# plug-v19-Make-board-myself-to-test-circu.net
KiCad netlist of a schematic drawn in EAGLE
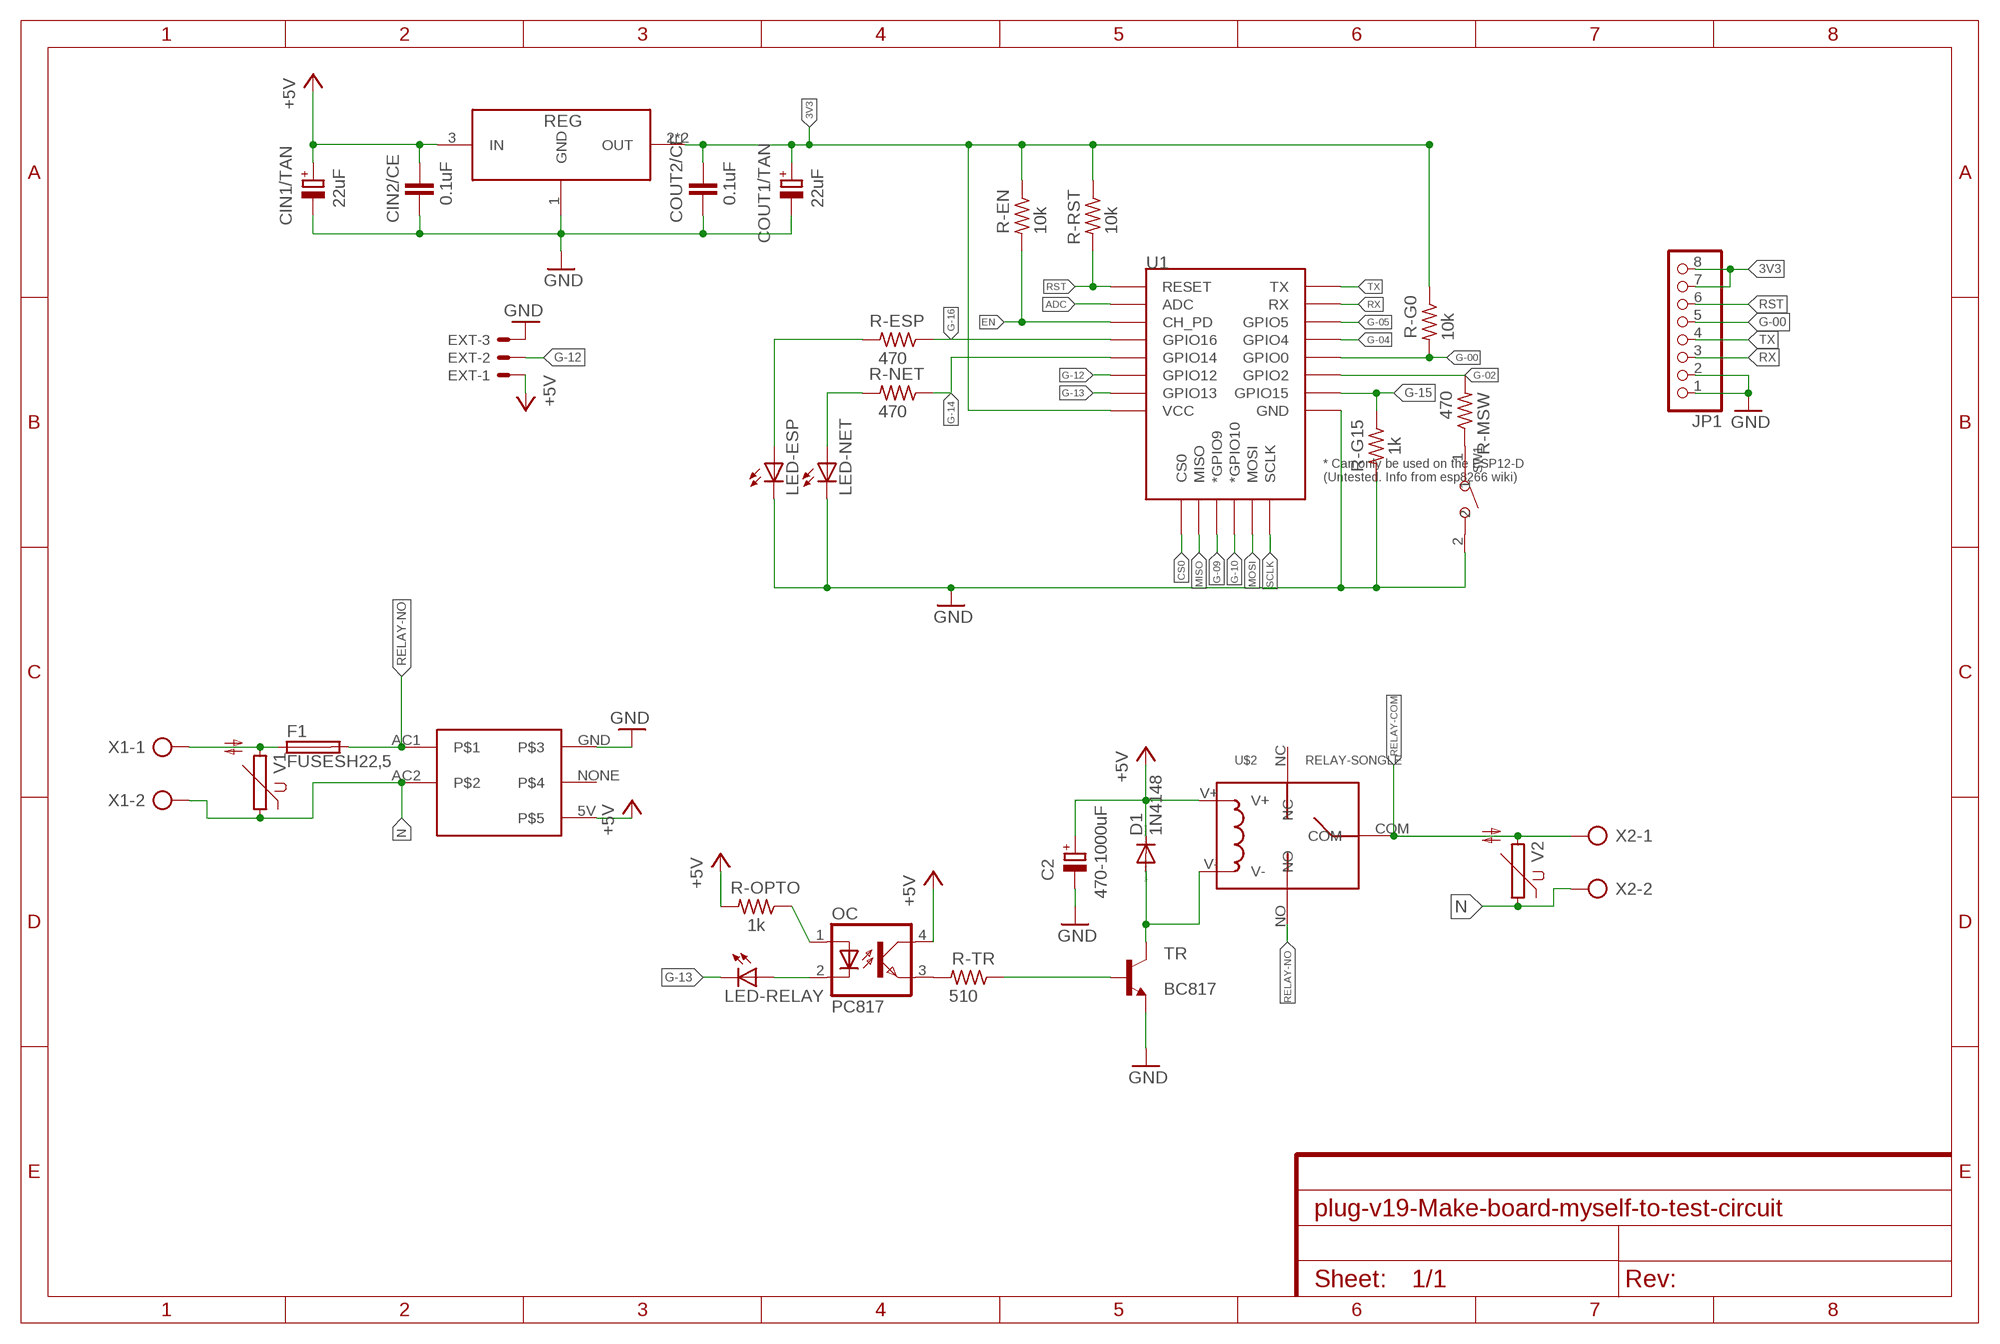
[diagram p0: schematic, sheet 1]

(export (version "E")
  (design (tool "Eeschema 10.0.6"))
  (components
    (comp (ref "C2")
      (value "470-1000uF")
      (footprint "eagle-import:E3,5-8")
      (libsource (lib "eagle-import") (part "CPOL-EUE3.5-8"))
    )
    (comp (ref "CIN1/TAN")
      (value "22uF")
      (footprint "eagle-import:B_3528-21R")
      (libsource (lib "eagle-import") (part "CPOL-EUB/3528-21R"))
    )
    (comp (ref "CIN2/CE")
      (value "0.1uF")
      (footprint "eagle-import:C0805K")
      (libsource (lib "eagle-import") (part "C-EUC0805K"))
    )
    (comp (ref "COUT1/TAN")
      (value "22uF")
      (footprint "eagle-import:B_3528-21R")
      (libsource (lib "eagle-import") (part "CPOL-EUB/3528-21R"))
    )
    (comp (ref "COUT2/CE")
      (value "0.1uF")
      (footprint "eagle-import:C0805K")
      (libsource (lib "eagle-import") (part "C-EUC0805K"))
    )
    (comp (ref "D1")
      (value "1N4148")
      (footprint "eagle-import:DO35-7")
      (libsource (lib "eagle-import") (part "1N4148DO35-7"))
    )
    (comp (ref "EXT")
      (value "53048-03")
      (footprint "eagle-import:53048-03")
      (fields (field (name "MF") "WALDOM/MOLEX") (field (name "MPN") "53048-0310"))
      (libsource (lib "eagle-import") (part "53?-03048"))
    )
    (comp (ref "F1")
      (value "FUSESH22,5")
      (footprint "eagle-import:SH22,5")
      (libsource (lib "eagle-import") (part "FUSESH22,5"))
    )
    (comp (ref "JP1")
      (value "PINHD-1X8")
      (footprint "eagle-import:1X08")
      (libsource (lib "eagle-import") (part "PINHD-1X8"))
    )
    (comp (ref "LED-ESP")
      (value "LEDCHIPLED_0805")
      (footprint "eagle-import:CHIPLED_0805")
      (libsource (lib "eagle-import") (part "LEDCHIPLED_0805"))
    )
    (comp (ref "LED-NET")
      (value "LEDCHIPLED_0805")
      (footprint "eagle-import:CHIPLED_0805")
      (libsource (lib "eagle-import") (part "LEDCHIPLED_0805"))
    )
    (comp (ref "LED-RELAY")
      (value "LEDCHIPLED_0805")
      (footprint "eagle-import:CHIPLED_0805")
      (libsource (lib "eagle-import") (part "LEDCHIPLED_0805"))
    )
    (comp (ref "OC")
      (value "PC817")
      (footprint "eagle-import:DIL04")
      (fields (field (name "MPN") "PC817X4J000F"))
      (libsource (lib "eagle-import") (part "PC817"))
    )
    (comp (ref "R-EN")
      (value "10k")
      (footprint "eagle-import:M0805")
      (libsource (lib "eagle-import") (part "R-US_M0805"))
    )
    (comp (ref "R-ESP")
      (value "470")
      (footprint "eagle-import:M0805")
      (libsource (lib "eagle-import") (part "R-US_M0805"))
    )
    (comp (ref "R-G0")
      (value "10k")
      (footprint "eagle-import:M0805")
      (libsource (lib "eagle-import") (part "R-US_M0805"))
    )
    (comp (ref "R-G15")
      (value "1k")
      (footprint "eagle-import:M0805")
      (libsource (lib "eagle-import") (part "R-US_M0805"))
    )
    (comp (ref "R-MSW")
      (value "470")
      (footprint "eagle-import:M0805")
      (libsource (lib "eagle-import") (part "R-US_M0805"))
    )
    (comp (ref "R-NET")
      (value "470")
      (footprint "eagle-import:M0805")
      (libsource (lib "eagle-import") (part "R-US_M0805"))
    )
    (comp (ref "R-OPTO")
      (value "1k")
      (footprint "eagle-import:M0805")
      (libsource (lib "eagle-import") (part "R-US_M0805"))
    )
    (comp (ref "R-RST")
      (value "10k")
      (footprint "eagle-import:M0805")
      (libsource (lib "eagle-import") (part "R-US_M0805"))
    )
    (comp (ref "R-TR")
      (value "510")
      (footprint "eagle-import:M0805")
      (libsource (lib "eagle-import") (part "R-US_M0805"))
    )
    (comp (ref "REG")
      (value "AMS1117-3.3")
      (footprint "eagle-import:SOT-223")
      (libsource (lib "eagle-import") (part "AMS1117-3.3"))
    )
    (comp (ref "SW1")
      (value "DIP-BUTTON(2P-6.0X3.0X4.3MM)-TS-1101F")
      (footprint "eagle-import:SW2-5.0-6.0X3.0X4.3MM")
      (libsource (lib "eagle-import") (part "DIP-BUTTON(2P-6.0X3.0X4.3MM)-TS-1101F"))
    )
    (comp (ref "TR")
      (value "BC817")
      (footprint "eagle-import:SOT23-BEC")
      (libsource (lib "eagle-import") (part "BC817SMD-16"))
    )
    (comp (ref "U$2")
      (value "RELAY-SONGLE")
      (footprint "eagle-import:RELAY-SONGLE")
      (libsource (lib "eagle-import") (part "RELAY-SONGLE"))
    )
    (comp (ref "U$4")
      (value "POWERSUPPLY-5V-700MA")
      (footprint "eagle-import:POWERSUPPLY-5V-700MA")
      (libsource (lib "eagle-import") (part "POWERSUPPLY-5V-700MA"))
    )
    (comp (ref "U1")
      (value "ESP12ESMD")
      (footprint "eagle-import:ESP12E-SMD")
      (libsource (lib "eagle-import") (part "ESP12ESMD"))
    )
    (comp (ref "V1")
      (value "S14K11")
      (footprint "eagle-import:S14K11")
      (libsource (lib "eagle-import") (part "S14K11"))
    )
    (comp (ref "V2")
      (value "S14K11")
      (footprint "eagle-import:S14K11")
      (libsource (lib "eagle-import") (part "S14K11"))
    )
    (comp (ref "X1")
      (value "AK300/2")
      (footprint "eagle-import:AK300_2")
      (libsource (lib "eagle-import") (part "AK300/2"))
    )
    (comp (ref "X2")
      (value "AK300/2")
      (footprint "eagle-import:AK300_2")
      (libsource (lib "eagle-import") (part "AK300/2"))
    )
  )
  (nets
    (net (code "1") (name "+5V") (class "Default")
      (node (ref "C2") (pin "+") (pinfunction "+_+") (pintype "passive"))
      (node (ref "CIN1/TAN") (pin "+") (pinfunction "+_+") (pintype "passive"))
      (node (ref "CIN2/CE") (pin "1") (pinfunction "1_1") (pintype "passive"))
      (node (ref "D1") (pin "C") (pinfunction "C_C") (pintype "passive"))
      (node (ref "EXT") (pin "1") (pinfunction "S_1") (pintype "passive"))
      (node (ref "OC") (pin "4") (pinfunction "COL_4") (pintype "passive"))
      (node (ref "R-OPTO") (pin "2") (pinfunction "2_2") (pintype "passive"))
      (node (ref "REG") (pin "3") (pinfunction "IN_3") (pintype "input"))
      (node (ref "U$2") (pin "V+") (pinfunction "V+_V+") (pintype "bidirectional"))
      (node (ref "U$4") (pin "5V") (pinfunction "P$5_5V") (pintype "bidirectional"))
    )
    (net (code "2") (name "3V3") (class "Default")
      (node (ref "COUT1/TAN") (pin "+") (pinfunction "+_+") (pintype "passive"))
      (node (ref "COUT2/CE") (pin "1") (pinfunction "1_1") (pintype "passive"))
      (node (ref "JP1") (pin "7") (pinfunction "7_7") (pintype "passive"))
      (node (ref "JP1") (pin "8") (pinfunction "8_8") (pintype "passive"))
      (node (ref "R-EN") (pin "1") (pinfunction "1_1") (pintype "passive"))
      (node (ref "R-G0") (pin "1") (pinfunction "1_1") (pintype "passive"))
      (node (ref "R-RST") (pin "1") (pinfunction "1_1") (pintype "passive"))
      (node (ref "REG") (pin "2") (pinfunction "OUT_2") (pintype "output"))
      (node (ref "REG") (pin "4") (pinfunction "OUT_4") (pintype "output"))
      (node (ref "U1") (pin "VCC") (pinfunction "VCC_VCC") (pintype "bidirectional"))
    )
    (net (code "3") (name "ADC") (class "Default")
      (node (ref "U1") (pin "ADC") (pinfunction "ADC_ADC") (pintype "bidirectional"))
    )
    (net (code "4") (name "CS0") (class "Default")
      (node (ref "U1") (pin "CS0") (pinfunction "CS0_CS0") (pintype "bidirectional"))
    )
    (net (code "5") (name "EN") (class "Default")
      (node (ref "R-EN") (pin "2") (pinfunction "2_2") (pintype "passive"))
      (node (ref "U1") (pin "CH_PD") (pinfunction "CH_PD_CH_PD") (pintype "bidirectional"))
    )
    (net (code "6") (name "G-00") (class "Default")
      (node (ref "JP1") (pin "5") (pinfunction "5_5") (pintype "passive"))
      (node (ref "R-G0") (pin "2") (pinfunction "2_2") (pintype "passive"))
      (node (ref "U1") (pin "GPIO0") (pinfunction "GPIO0_GPIO0") (pintype "bidirectional"))
    )
    (net (code "7") (name "G-02") (class "Default")
      (node (ref "R-MSW") (pin "2") (pinfunction "2_2") (pintype "passive"))
      (node (ref "U1") (pin "GPIO2") (pinfunction "GPIO2_GPIO2") (pintype "bidirectional"))
    )
    (net (code "8") (name "G-04") (class "Default")
      (node (ref "U1") (pin "GPIO4") (pinfunction "GPIO4_GPIO4") (pintype "bidirectional"))
    )
    (net (code "9") (name "G-05") (class "Default")
      (node (ref "U1") (pin "GPIO5") (pinfunction "GPIO5_GPIO5") (pintype "bidirectional"))
    )
    (net (code "10") (name "G-09") (class "Default")
      (node (ref "U1") (pin "GPIO9") (pinfunction "*GPIO9_GPIO9") (pintype "bidirectional"))
    )
    (net (code "11") (name "G-10") (class "Default")
      (node (ref "U1") (pin "GPIO10") (pinfunction "*GPIO10_GPIO10") (pintype "bidirectional"))
    )
    (net (code "12") (name "G-12") (class "Default")
      (node (ref "EXT") (pin "2") (pinfunction "S_2") (pintype "passive"))
      (node (ref "U1") (pin "GPIO12") (pinfunction "GPIO12_GPIO12") (pintype "bidirectional"))
    )
    (net (code "13") (name "G-13") (class "Default")
      (node (ref "LED-RELAY") (pin "C") (pinfunction "C_C") (pintype "passive"))
      (node (ref "U1") (pin "GPIO13") (pinfunction "GPIO13_GPIO13") (pintype "bidirectional"))
    )
    (net (code "14") (name "G-14") (class "Default")
      (node (ref "R-NET") (pin "1") (pinfunction "1_1") (pintype "passive"))
      (node (ref "U1") (pin "GPIO14") (pinfunction "GPIO14_GPIO14") (pintype "bidirectional"))
    )
    (net (code "15") (name "G-15") (class "Default")
      (node (ref "R-G15") (pin "1") (pinfunction "1_1") (pintype "passive"))
      (node (ref "U1") (pin "GPIO15") (pinfunction "GPIO15_GPIO15") (pintype "bidirectional"))
    )
    (net (code "16") (name "G-16") (class "Default")
      (node (ref "R-ESP") (pin "1") (pinfunction "1_1") (pintype "passive"))
      (node (ref "U1") (pin "GPIO16") (pinfunction "GPIO16_GPIO16") (pintype "bidirectional"))
    )
    (net (code "17") (name "GND") (class "Default")
      (node (ref "C2") (pin "-") (pinfunction "-_-") (pintype "passive"))
      (node (ref "CIN1/TAN") (pin "-") (pinfunction "-_-") (pintype "passive"))
      (node (ref "CIN2/CE") (pin "2") (pinfunction "2_2") (pintype "passive"))
      (node (ref "COUT1/TAN") (pin "-") (pinfunction "-_-") (pintype "passive"))
      (node (ref "COUT2/CE") (pin "2") (pinfunction "2_2") (pintype "passive"))
      (node (ref "EXT") (pin "3") (pinfunction "S_3") (pintype "passive"))
      (node (ref "JP1") (pin "1") (pinfunction "1_1") (pintype "passive"))
      (node (ref "JP1") (pin "2") (pinfunction "2_2") (pintype "passive"))
      (node (ref "LED-ESP") (pin "C") (pinfunction "C_C") (pintype "passive"))
      (node (ref "LED-NET") (pin "C") (pinfunction "C_C") (pintype "passive"))
      (node (ref "R-G15") (pin "2") (pinfunction "2_2") (pintype "passive"))
      (node (ref "REG") (pin "1") (pinfunction "GND_1") (pintype "passive"))
      (node (ref "SW1") (pin "2") (pinfunction "2_2") (pintype "bidirectional"))
      (node (ref "TR") (pin "E") (pinfunction "E_E") (pintype "passive"))
      (node (ref "U$4") (pin "GND") (pinfunction "P$3_GND") (pintype "bidirectional"))
      (node (ref "U1") (pin "GND") (pinfunction "GND_GND") (pintype "bidirectional"))
    )
    (net (code "18") (name "MISO") (class "Default")
      (node (ref "U1") (pin "MISO") (pinfunction "MISO_MISO") (pintype "bidirectional"))
    )
    (net (code "19") (name "MOSI") (class "Default")
      (node (ref "U1") (pin "MOSI") (pinfunction "MOSI_MOSI") (pintype "bidirectional"))
    )
    (net (code "20") (name "N") (class "Default")
      (node (ref "U$4") (pin "AC2") (pinfunction "P$2_AC2") (pintype "bidirectional"))
      (node (ref "V1") (pin "1") (pinfunction "1_1") (pintype "passive"))
      (node (ref "V2") (pin "1") (pinfunction "1_1") (pintype "passive"))
      (node (ref "X1") (pin "2") (pinfunction "KL_2") (pintype "passive"))
      (node (ref "X2") (pin "2") (pinfunction "KL_2") (pintype "passive"))
    )
    (net (code "21") (name "Net-(D1-PadA)") (class "Default")
      (node (ref "D1") (pin "A") (pinfunction "A_A") (pintype "passive"))
      (node (ref "TR") (pin "C") (pinfunction "C_C") (pintype "passive"))
      (node (ref "U$2") (pin "V-") (pinfunction "V-_V-") (pintype "bidirectional"))
    )
    (net (code "22") (name "Net-(LED-ESP-PadA)") (class "Default")
      (node (ref "LED-ESP") (pin "A") (pinfunction "A_A") (pintype "passive"))
      (node (ref "R-ESP") (pin "2") (pinfunction "2_2") (pintype "passive"))
    )
    (net (code "23") (name "Net-(LED-NET-PadA)") (class "Default")
      (node (ref "LED-NET") (pin "A") (pinfunction "A_A") (pintype "passive"))
      (node (ref "R-NET") (pin "2") (pinfunction "2_2") (pintype "passive"))
    )
    (net (code "24") (name "Net-(OC-A)") (class "Default")
      (node (ref "OC") (pin "1") (pinfunction "A_1") (pintype "passive"))
      (node (ref "R-OPTO") (pin "1") (pinfunction "1_1") (pintype "passive"))
    )
    (net (code "25") (name "Net-(OC-C)") (class "Default")
      (node (ref "LED-RELAY") (pin "A") (pinfunction "A_A") (pintype "passive"))
      (node (ref "OC") (pin "2") (pinfunction "C_2") (pintype "passive"))
    )
    (net (code "26") (name "Net-(OC-EMIT)") (class "Default")
      (node (ref "OC") (pin "3") (pinfunction "EMIT_3") (pintype "passive"))
      (node (ref "R-TR") (pin "2") (pinfunction "2_2") (pintype "passive"))
    )
    (net (code "27") (name "Net-(R-MSW-Pad1)") (class "Default")
      (node (ref "R-MSW") (pin "1") (pinfunction "1_1") (pintype "passive"))
      (node (ref "SW1") (pin "1") (pinfunction "1_1") (pintype "bidirectional"))
    )
    (net (code "28") (name "Net-(R-TR-Pad1)") (class "Default")
      (node (ref "R-TR") (pin "1") (pinfunction "1_1") (pintype "passive"))
      (node (ref "TR") (pin "B") (pinfunction "B_B") (pintype "passive"))
    )
    (net (code "29") (name "Net-(X1A-KL)") (class "Default")
      (node (ref "F1") (pin "1") (pinfunction "1_1") (pintype "passive"))
      (node (ref "V1") (pin "2") (pinfunction "2_2") (pintype "passive"))
      (node (ref "X1") (pin "1") (pinfunction "KL_1") (pintype "passive"))
    )
    (net (code "30") (name "RELAY-COM") (class "Default")
      (node (ref "U$2") (pin "COM") (pinfunction "COM_COM") (pintype "bidirectional"))
      (node (ref "V2") (pin "2") (pinfunction "2_2") (pintype "passive"))
      (node (ref "X2") (pin "1") (pinfunction "KL_1") (pintype "passive"))
    )
    (net (code "31") (name "RELAY-NO") (class "Default")
      (node (ref "F1") (pin "2") (pinfunction "2_2") (pintype "passive"))
      (node (ref "U$2") (pin "NO") (pinfunction "NO_NO") (pintype "bidirectional"))
      (node (ref "U$4") (pin "AC1") (pinfunction "P$1_AC1") (pintype "bidirectional"))
    )
    (net (code "32") (name "RST") (class "Default")
      (node (ref "JP1") (pin "6") (pinfunction "6_6") (pintype "passive"))
      (node (ref "R-RST") (pin "2") (pinfunction "2_2") (pintype "passive"))
      (node (ref "U1") (pin "RESET") (pinfunction "RESET_RESET") (pintype "bidirectional"))
    )
    (net (code "33") (name "RX") (class "Default")
      (node (ref "JP1") (pin "3") (pinfunction "3_3") (pintype "passive"))
      (node (ref "U1") (pin "RXD0") (pinfunction "RX_RXD0") (pintype "bidirectional"))
    )
    (net (code "34") (name "SCLK") (class "Default")
      (node (ref "U1") (pin "SCLK") (pinfunction "SCLK_SCLK") (pintype "bidirectional"))
    )
    (net (code "35") (name "TX") (class "Default")
      (node (ref "JP1") (pin "4") (pinfunction "4_4") (pintype "passive"))
      (node (ref "U1") (pin "TXD0") (pinfunction "TX_TXD0") (pintype "bidirectional"))
    )
    (net (code "36") (name "unconnected-(U$2-PadNC)") (class "Default")
      (node (ref "U$2") (pin "NC") (pinfunction "NC_NC") (pintype "bidirectional"))
    )
    (net (code "37") (name "unconnected-(U$4-P$4-PadNONE)") (class "Default")
      (node (ref "U$4") (pin "NONE") (pinfunction "P$4_NONE") (pintype "bidirectional"))
    )
  )
)
